# hdmi_fpc_rev1.net
KiCad netlist of a schematic drawn in EAGLE
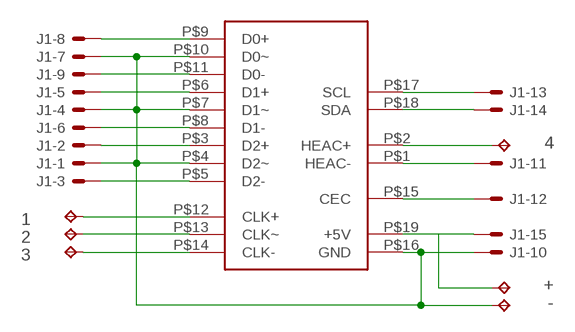
[diagram p0: schematic, sheet 1]

(export (version "E")
  (design (tool "Eeschema 10.0.6"))
  (components
    (comp (ref "+")
      (value "TPPAD1-13")
      (footprint "eagle-import:P1-13")
      (libsource (lib "eagle-import") (part "TPPAD1-13"))
    )
    (comp (ref "-")
      (value "TPPAD1-13")
      (footprint "eagle-import:P1-13")
      (libsource (lib "eagle-import") (part "TPPAD1-13"))
    )
    (comp (ref "1")
      (value "TPPAD1-13")
      (footprint "eagle-import:P1-13")
      (libsource (lib "eagle-import") (part "TPPAD1-13"))
    )
    (comp (ref "2")
      (value "TPPAD1-13")
      (footprint "eagle-import:P1-13")
      (libsource (lib "eagle-import") (part "TPPAD1-13"))
    )
    (comp (ref "3")
      (value "TPPAD1-13")
      (footprint "eagle-import:P1-13")
      (libsource (lib "eagle-import") (part "TPPAD1-13"))
    )
    (comp (ref "4")
      (value "TPPAD1-13")
      (footprint "eagle-import:P1-13")
      (libsource (lib "eagle-import") (part "TPPAD1-13"))
    )
    (comp (ref "J1")
      (value "XF2L-1535-1")
      (footprint "eagle-import:XF2L-1535-1")
      (fields (field (name "MPN") "XF2L-1535-1A"))
      (libsource (lib "eagle-import") (part "XF2-15?35-1L"))
    )
    (comp (ref "U$1")
      (value "HDMI_MICRO")
      (footprint "eagle-import:MICRO_HDMI")
      (libsource (lib "eagle-import") (part "HDMI_MICRO"))
    )
  )
  (nets
    (net (code "1") (name "Net-(J1A-MSV)") (class "Default")
      (node (ref "-") (pin "TP") (pinfunction "TP_TP") (pintype "input"))
      (node (ref "J1") (pin "1") (pinfunction "MSV_1") (pintype "passive"))
      (node (ref "J1") (pin "10") (pinfunction "MS_10") (pintype "passive"))
      (node (ref "J1") (pin "4") (pinfunction "MS_4") (pintype "passive"))
      (node (ref "J1") (pin "7") (pinfunction "MS_7") (pintype "passive"))
      (node (ref "U$1") (pin "P$10") (pinfunction "D0~{}_P$10") (pintype "bidirectional"))
      (node (ref "U$1") (pin "P$16") (pinfunction "GND_P$16") (pintype "bidirectional"))
      (node (ref "U$1") (pin "P$4") (pinfunction "D2~{}_P$4") (pintype "bidirectional"))
      (node (ref "U$1") (pin "P$7") (pinfunction "D1~{}_P$7") (pintype "bidirectional"))
    )
    (net (code "2") (name "Net-(J1C-MS)") (class "Default")
      (node (ref "J1") (pin "11") (pinfunction "MS_11") (pintype "passive"))
      (node (ref "U$1") (pin "P$1") (pinfunction "HEAC-_P$1") (pintype "bidirectional"))
    )
    (net (code "3") (name "Net-(J1D-MS)") (class "Default")
      (node (ref "J1") (pin "12") (pinfunction "MS_12") (pintype "passive"))
      (node (ref "U$1") (pin "P$15") (pinfunction "CEC_P$15") (pintype "bidirectional"))
    )
    (net (code "4") (name "Net-(J1E-MS)") (class "Default")
      (node (ref "J1") (pin "13") (pinfunction "MS_13") (pintype "passive"))
      (node (ref "U$1") (pin "P$17") (pinfunction "SCL_P$17") (pintype "bidirectional"))
    )
    (net (code "5") (name "Net-(J1F-MS)") (class "Default")
      (node (ref "J1") (pin "14") (pinfunction "MS_14") (pintype "passive"))
      (node (ref "U$1") (pin "P$18") (pinfunction "SDA_P$18") (pintype "bidirectional"))
    )
    (net (code "6") (name "Net-(J1G-MS)") (class "Default")
      (node (ref "+") (pin "TP") (pinfunction "TP_TP") (pintype "input"))
      (node (ref "J1") (pin "15") (pinfunction "MS_15") (pintype "passive"))
      (node (ref "U$1") (pin "P$19") (pinfunction "+5V_P$19") (pintype "bidirectional"))
    )
    (net (code "7") (name "Net-(J1H-MS)") (class "Default")
      (node (ref "J1") (pin "2") (pinfunction "MS_2") (pintype "passive"))
      (node (ref "U$1") (pin "P$3") (pinfunction "D2+_P$3") (pintype "bidirectional"))
    )
    (net (code "8") (name "Net-(J1I-MS)") (class "Default")
      (node (ref "J1") (pin "3") (pinfunction "MS_3") (pintype "passive"))
      (node (ref "U$1") (pin "P$5") (pinfunction "D2-_P$5") (pintype "bidirectional"))
    )
    (net (code "9") (name "Net-(J1K-MS)") (class "Default")
      (node (ref "J1") (pin "5") (pinfunction "MS_5") (pintype "passive"))
      (node (ref "U$1") (pin "P$6") (pinfunction "D1+_P$6") (pintype "bidirectional"))
    )
    (net (code "10") (name "Net-(J1L-MS)") (class "Default")
      (node (ref "J1") (pin "6") (pinfunction "MS_6") (pintype "passive"))
      (node (ref "U$1") (pin "P$8") (pinfunction "D1-_P$8") (pintype "bidirectional"))
    )
    (net (code "11") (name "Net-(J1N-MS)") (class "Default")
      (node (ref "J1") (pin "8") (pinfunction "MS_8") (pintype "passive"))
      (node (ref "U$1") (pin "P$9") (pinfunction "D0+_P$9") (pintype "bidirectional"))
    )
    (net (code "12") (name "Net-(J1O-MS)") (class "Default")
      (node (ref "J1") (pin "9") (pinfunction "MS_9") (pintype "passive"))
      (node (ref "U$1") (pin "P$11") (pinfunction "D0-_P$11") (pintype "bidirectional"))
    )
    (net (code "13") (name "Net-(U$1-CLK+)") (class "Default")
      (node (ref "1") (pin "TP") (pinfunction "TP_TP") (pintype "input"))
      (node (ref "U$1") (pin "P$12") (pinfunction "CLK+_P$12") (pintype "bidirectional"))
    )
    (net (code "14") (name "Net-(U$1-CLK-)") (class "Default")
      (node (ref "3") (pin "TP") (pinfunction "TP_TP") (pintype "input"))
      (node (ref "U$1") (pin "P$14") (pinfunction "CLK-_P$14") (pintype "bidirectional"))
    )
    (net (code "15") (name "Net-(U$1-CLK~{})") (class "Default")
      (node (ref "2") (pin "TP") (pinfunction "TP_TP") (pintype "input"))
      (node (ref "U$1") (pin "P$13") (pinfunction "CLK~{}_P$13") (pintype "bidirectional"))
    )
    (net (code "16") (name "Net-(U$1-HEAC+)") (class "Default")
      (node (ref "4") (pin "TP") (pinfunction "TP_TP") (pintype "input"))
      (node (ref "U$1") (pin "P$2") (pinfunction "HEAC+_P$2") (pintype "bidirectional"))
    )
  )
)
